# Beambreak_Array_L_-_Receiver.net
KiCad netlist of a schematic drawn in Altium Designer
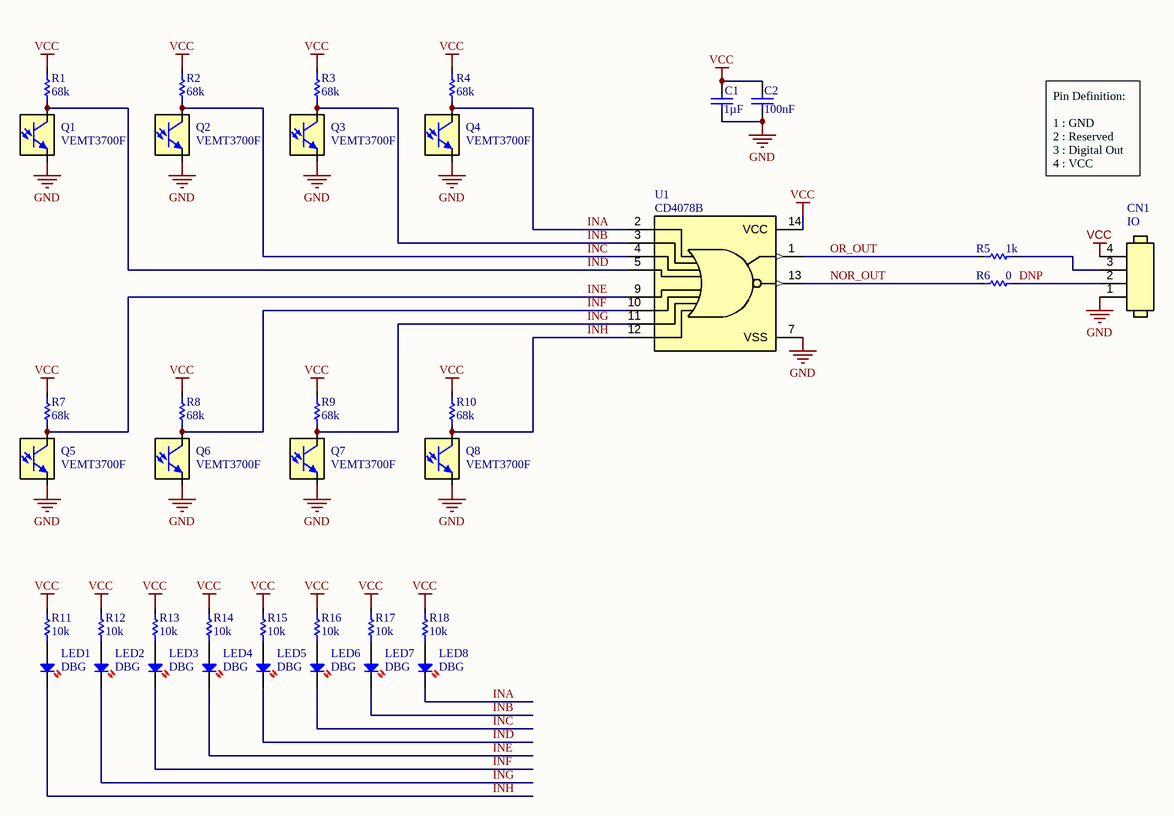
[diagram p0: Beambreak Array L - Receiver.SchDoc]

(export (version "E")
  (design (tool "Eeschema 10.0.6"))
  (components
    (comp (ref "C1")
      (value "1µF")
      (footprint "CAP_CHIP_0603")
      (description "0603 Multilayer Ceramic Capacitors MLCC")
      (fields (field (name "PARTNUMBER") "CL10A105KB8NNNC") (field (name "TOLERANCE") "10%"))
      (libsource (lib "Sainsbury Wellcome Centre") (part "Cap"))
    )
    (comp (ref "C2")
      (value "100nF")
      (footprint "CAP_CHIP_0603")
      (description "0603 Multilayer Ceramic Capacitors MLCC")
      (fields (field (name "TOLERANCE") "10%") (field (name "PARTNUMBER") "CC0603KRX7R9BB104"))
      (libsource (lib "Sainsbury Wellcome Centre") (part "Cap"))
    )
    (comp (ref "CN1")
      (value "IO")
      (footprint "MOLEX_1.25_4P")
      (description "Conn Shrouded Header (3 Sides) HDR 4 POS 1.25mm Solder ST Top Entry SMD PicoBlade™ T/R")
      (fields (field (name "PARTNUMBER") "53398-0471"))
      (libsource (lib "Sainsbury Wellcome Centre") (part "Wire to Board 1x4"))
    )
    (comp (ref "LED1")
      (value "DBG")
      (footprint "LED_CHIP_0805")
      (description "Red 0805 Light Emitting Diodes (LED) ROHS")
      (fields (field (name "PARTNUMBER") "NCD0805R1"))
      (libsource (lib "Sainsbury Wellcome Centre") (part "LED-RED"))
    )
    (comp (ref "LED2")
      (value "DBG")
      (footprint "LED_CHIP_0805")
      (description "Red 0805 Light Emitting Diodes (LED) ROHS")
      (fields (field (name "PARTNUMBER") "NCD0805R1"))
      (libsource (lib "Sainsbury Wellcome Centre") (part "LED-RED"))
    )
    (comp (ref "LED3")
      (value "DBG")
      (footprint "LED_CHIP_0805")
      (description "Red 0805 Light Emitting Diodes (LED) ROHS")
      (fields (field (name "PARTNUMBER") "NCD0805R1"))
      (libsource (lib "Sainsbury Wellcome Centre") (part "LED-RED"))
    )
    (comp (ref "LED4")
      (value "DBG")
      (footprint "LED_CHIP_0805")
      (description "Red 0805 Light Emitting Diodes (LED) ROHS")
      (fields (field (name "PARTNUMBER") "NCD0805R1"))
      (libsource (lib "Sainsbury Wellcome Centre") (part "LED-RED"))
    )
    (comp (ref "LED5")
      (value "DBG")
      (footprint "LED_CHIP_0805")
      (description "Red 0805 Light Emitting Diodes (LED) ROHS")
      (fields (field (name "PARTNUMBER") "NCD0805R1"))
      (libsource (lib "Sainsbury Wellcome Centre") (part "LED-RED"))
    )
    (comp (ref "LED6")
      (value "DBG")
      (footprint "LED_CHIP_0805")
      (description "Red 0805 Light Emitting Diodes (LED) ROHS")
      (fields (field (name "PARTNUMBER") "NCD0805R1"))
      (libsource (lib "Sainsbury Wellcome Centre") (part "LED-RED"))
    )
    (comp (ref "LED7")
      (value "DBG")
      (footprint "LED_CHIP_0805")
      (description "Red 0805 Light Emitting Diodes (LED) ROHS")
      (fields (field (name "PARTNUMBER") "NCD0805R1"))
      (libsource (lib "Sainsbury Wellcome Centre") (part "LED-RED"))
    )
    (comp (ref "LED8")
      (value "DBG")
      (footprint "LED_CHIP_0805")
      (description "Red 0805 Light Emitting Diodes (LED) ROHS")
      (fields (field (name "PARTNUMBER") "NCD0805R1"))
      (libsource (lib "Sainsbury Wellcome Centre") (part "LED-RED"))
    )
    (comp (ref "Q1")
      (value "VEMT3700F")
      (footprint "PT_3528_NPN")
      (description "No Phototransistor IR Chip Silicon 940nm 2-Pin PLCC T/R")
      (fields (field (name "PARTNUMBER") "VEMT3700F-GS08"))
      (libsource (lib "Sainsbury Wellcome Centre") (part "Phototransistors_1C2E"))
    )
    (comp (ref "Q2")
      (value "VEMT3700F")
      (footprint "PT_3528_NPN")
      (description "No Phototransistor IR Chip Silicon 940nm 2-Pin PLCC T/R")
      (fields (field (name "PARTNUMBER") "VEMT3700F-GS08"))
      (libsource (lib "Sainsbury Wellcome Centre") (part "Phototransistors_1C2E"))
    )
    (comp (ref "Q3")
      (value "VEMT3700F")
      (footprint "PT_3528_NPN")
      (description "No Phototransistor IR Chip Silicon 940nm 2-Pin PLCC T/R")
      (fields (field (name "PARTNUMBER") "VEMT3700F-GS08"))
      (libsource (lib "Sainsbury Wellcome Centre") (part "Phototransistors_1C2E"))
    )
    (comp (ref "Q4")
      (value "VEMT3700F")
      (footprint "PT_3528_NPN")
      (description "No Phototransistor IR Chip Silicon 940nm 2-Pin PLCC T/R")
      (fields (field (name "PARTNUMBER") "VEMT3700F-GS08"))
      (libsource (lib "Sainsbury Wellcome Centre") (part "Phototransistors_1C2E"))
    )
    (comp (ref "Q5")
      (value "VEMT3700F")
      (footprint "PT_3528_NPN")
      (description "No Phototransistor IR Chip Silicon 940nm 2-Pin PLCC T/R")
      (fields (field (name "PARTNUMBER") "VEMT3700F-GS08"))
      (libsource (lib "Sainsbury Wellcome Centre") (part "Phototransistors_1C2E"))
    )
    (comp (ref "Q6")
      (value "VEMT3700F")
      (footprint "PT_3528_NPN")
      (description "No Phototransistor IR Chip Silicon 940nm 2-Pin PLCC T/R")
      (fields (field (name "PARTNUMBER") "VEMT3700F-GS08"))
      (libsource (lib "Sainsbury Wellcome Centre") (part "Phototransistors_1C2E"))
    )
    (comp (ref "Q7")
      (value "VEMT3700F")
      (footprint "PT_3528_NPN")
      (description "No Phototransistor IR Chip Silicon 940nm 2-Pin PLCC T/R")
      (fields (field (name "PARTNUMBER") "VEMT3700F-GS08"))
      (libsource (lib "Sainsbury Wellcome Centre") (part "Phototransistors_1C2E"))
    )
    (comp (ref "Q8")
      (value "VEMT3700F")
      (footprint "PT_3528_NPN")
      (description "No Phototransistor IR Chip Silicon 940nm 2-Pin PLCC T/R")
      (fields (field (name "PARTNUMBER") "VEMT3700F-GS08"))
      (libsource (lib "Sainsbury Wellcome Centre") (part "Phototransistors_1C2E"))
    )
    (comp (ref "R1")
      (value "68k")
      (footprint "RES_CHIP_0603")
      (description "100mW Thick Film Resistors 75V ±100ppm/℃ ±1% 0603 Chip Resistor")
      (fields (field (name "TOLERANCE") "1%") (field (name "PARTNUMBER") "0603WAF6802T5E"))
      (libsource (lib "Sainsbury Wellcome Centre") (part "Res"))
    )
    (comp (ref "R2")
      (value "68k")
      (footprint "RES_CHIP_0603")
      (description "100mW Thick Film Resistors 75V ±100ppm/℃ ±1% 0603 Chip Resistor")
      (fields (field (name "TOLERANCE") "1%") (field (name "PARTNUMBER") "0603WAF6802T5E"))
      (libsource (lib "Sainsbury Wellcome Centre") (part "Res"))
    )
    (comp (ref "R3")
      (value "68k")
      (footprint "RES_CHIP_0603")
      (description "100mW Thick Film Resistors 75V ±100ppm/℃ ±1% 0603 Chip Resistor")
      (fields (field (name "TOLERANCE") "1%") (field (name "PARTNUMBER") "0603WAF6802T5E"))
      (libsource (lib "Sainsbury Wellcome Centre") (part "Res"))
    )
    (comp (ref "R4")
      (value "68k")
      (footprint "RES_CHIP_0603")
      (description "100mW Thick Film Resistors 75V ±100ppm/℃ ±1% 0603 Chip Resistor")
      (fields (field (name "TOLERANCE") "1%") (field (name "PARTNUMBER") "0603WAF6802T5E"))
      (libsource (lib "Sainsbury Wellcome Centre") (part "Res"))
    )
    (comp (ref "R5")
      (value "1k")
      (footprint "RES_CHIP_0603")
      (description "100mW Thick Film Resistors 75V ±100ppm/℃ ±1% 0603 Chip Resistor")
      (fields (field (name "PARTNUMBER") "0603WAF1001T5E") (field (name "TOLERANCE") "1%"))
      (libsource (lib "Sainsbury Wellcome Centre") (part "Res"))
    )
    (comp (ref "R6")
      (value "0")
      (footprint "RES_CHIP_0603")
      (description "100mW Thick Film Resistors 75V ±100ppm/℃ ±1% 0603 Chip Resistor")
      (fields
        (field (name "TOLERANCE") "1%")
        (field (name "PARTNUMBER") "0603WAF0000T5E")
        (field (name "LCSC PART N.") "DNP")
      )
      (libsource (lib "Sainsbury Wellcome Centre") (part "Res"))
    )
    (comp (ref "R7")
      (value "68k")
      (footprint "RES_CHIP_0603")
      (description "100mW Thick Film Resistors 75V ±100ppm/℃ ±1% 0603 Chip Resistor")
      (fields (field (name "TOLERANCE") "1%") (field (name "PARTNUMBER") "0603WAF6802T5E"))
      (libsource (lib "Sainsbury Wellcome Centre") (part "Res"))
    )
    (comp (ref "R8")
      (value "68k")
      (footprint "RES_CHIP_0603")
      (description "100mW Thick Film Resistors 75V ±100ppm/℃ ±1% 0603 Chip Resistor")
      (fields (field (name "TOLERANCE") "1%") (field (name "PARTNUMBER") "0603WAF6802T5E"))
      (libsource (lib "Sainsbury Wellcome Centre") (part "Res"))
    )
    (comp (ref "R9")
      (value "68k")
      (footprint "RES_CHIP_0603")
      (description "100mW Thick Film Resistors 75V ±100ppm/℃ ±1% 0603 Chip Resistor")
      (fields (field (name "TOLERANCE") "1%") (field (name "PARTNUMBER") "0603WAF6802T5E"))
      (libsource (lib "Sainsbury Wellcome Centre") (part "Res"))
    )
    (comp (ref "R10")
      (value "68k")
      (footprint "RES_CHIP_0603")
      (description "100mW Thick Film Resistors 75V ±100ppm/℃ ±1% 0603 Chip Resistor")
      (fields (field (name "TOLERANCE") "1%") (field (name "PARTNUMBER") "0603WAF6802T5E"))
      (libsource (lib "Sainsbury Wellcome Centre") (part "Res"))
    )
    (comp (ref "R11")
      (value "10k")
      (footprint "RES_CHIP_0603")
      (description "100mW Thick Film Resistors 75V ±100ppm/℃ ±1% 0603 Chip Resistor")
      (fields (field (name "PARTNUMBER") "0603WAF1002T5E") (field (name "TOLERANCE") "1%"))
      (libsource (lib "Sainsbury Wellcome Centre") (part "Res"))
    )
    (comp (ref "R12")
      (value "10k")
      (footprint "RES_CHIP_0603")
      (description "100mW Thick Film Resistors 75V ±100ppm/℃ ±1% 0603 Chip Resistor")
      (fields (field (name "PARTNUMBER") "0603WAF1002T5E") (field (name "TOLERANCE") "1%"))
      (libsource (lib "Sainsbury Wellcome Centre") (part "Res"))
    )
    (comp (ref "R13")
      (value "10k")
      (footprint "RES_CHIP_0603")
      (description "100mW Thick Film Resistors 75V ±100ppm/℃ ±1% 0603 Chip Resistor")
      (fields (field (name "PARTNUMBER") "0603WAF1002T5E") (field (name "TOLERANCE") "1%"))
      (libsource (lib "Sainsbury Wellcome Centre") (part "Res"))
    )
    (comp (ref "R14")
      (value "10k")
      (footprint "RES_CHIP_0603")
      (description "100mW Thick Film Resistors 75V ±100ppm/℃ ±1% 0603 Chip Resistor")
      (fields (field (name "PARTNUMBER") "0603WAF1002T5E") (field (name "TOLERANCE") "1%"))
      (libsource (lib "Sainsbury Wellcome Centre") (part "Res"))
    )
    (comp (ref "R15")
      (value "10k")
      (footprint "RES_CHIP_0603")
      (description "100mW Thick Film Resistors 75V ±100ppm/℃ ±1% 0603 Chip Resistor")
      (fields (field (name "PARTNUMBER") "0603WAF1002T5E") (field (name "TOLERANCE") "1%"))
      (libsource (lib "Sainsbury Wellcome Centre") (part "Res"))
    )
    (comp (ref "R16")
      (value "10k")
      (footprint "RES_CHIP_0603")
      (description "100mW Thick Film Resistors 75V ±100ppm/℃ ±1% 0603 Chip Resistor")
      (fields (field (name "PARTNUMBER") "0603WAF1002T5E") (field (name "TOLERANCE") "1%"))
      (libsource (lib "Sainsbury Wellcome Centre") (part "Res"))
    )
    (comp (ref "R17")
      (value "10k")
      (footprint "RES_CHIP_0603")
      (description "100mW Thick Film Resistors 75V ±100ppm/℃ ±1% 0603 Chip Resistor")
      (fields (field (name "PARTNUMBER") "0603WAF1002T5E") (field (name "TOLERANCE") "1%"))
      (libsource (lib "Sainsbury Wellcome Centre") (part "Res"))
    )
    (comp (ref "R18")
      (value "10k")
      (footprint "RES_CHIP_0603")
      (description "100mW Thick Film Resistors 75V ±100ppm/℃ ±1% 0603 Chip Resistor")
      (fields (field (name "PARTNUMBER") "0603WAF1002T5E") (field (name "TOLERANCE") "1%"))
      (libsource (lib "Sainsbury Wellcome Centre") (part "Res"))
    )
    (comp (ref "U1")
      (value "CD4078B")
      (footprint "SOIC14")
      (description "IC GATE NOR/OR 8INPUT 14SOIC NOR/OR Gate Configurable 1 Circuit 8 Input 14-SOIC")
      (fields (field (name "PARTNUMBER") "CD4078BM96"))
      (libsource (lib "Sainsbury Wellcome Centre") (part "CD4078B"))
    )
  )
  (nets
    (net (code "1") (name "/INA") (class "Default")
      (node (ref "LED8") (pin "1") (pinfunction "K_1") (pintype "passive"))
      (node (ref "Q4") (pin "1") (pinfunction "C_1") (pintype "passive"))
      (node (ref "R4") (pin "1") (pinfunction "1_1") (pintype "passive"))
      (node (ref "U1") (pin "2") (pinfunction "1A_2") (pintype "passive"))
    )
    (net (code "2") (name "/INB") (class "Default")
      (node (ref "LED7") (pin "1") (pinfunction "K_1") (pintype "passive"))
      (node (ref "Q3") (pin "1") (pinfunction "C_1") (pintype "passive"))
      (node (ref "R3") (pin "1") (pinfunction "1_1") (pintype "passive"))
      (node (ref "U1") (pin "3") (pinfunction "1A_3") (pintype "passive"))
    )
    (net (code "3") (name "/INC") (class "Default")
      (node (ref "LED6") (pin "1") (pinfunction "K_1") (pintype "passive"))
      (node (ref "Q2") (pin "1") (pinfunction "C_1") (pintype "passive"))
      (node (ref "R2") (pin "1") (pinfunction "1_1") (pintype "passive"))
      (node (ref "U1") (pin "4") (pinfunction "1A_4") (pintype "passive"))
    )
    (net (code "4") (name "/IND") (class "Default")
      (node (ref "LED5") (pin "1") (pinfunction "K_1") (pintype "passive"))
      (node (ref "Q1") (pin "1") (pinfunction "C_1") (pintype "passive"))
      (node (ref "R1") (pin "1") (pinfunction "1_1") (pintype "passive"))
      (node (ref "U1") (pin "5") (pinfunction "1A_5") (pintype "passive"))
    )
    (net (code "5") (name "/INE") (class "Default")
      (node (ref "LED4") (pin "1") (pinfunction "K_1") (pintype "passive"))
      (node (ref "Q5") (pin "1") (pinfunction "C_1") (pintype "passive"))
      (node (ref "R7") (pin "1") (pinfunction "1_1") (pintype "passive"))
      (node (ref "U1") (pin "9") (pinfunction "1B_9") (pintype "passive"))
    )
    (net (code "6") (name "/INF") (class "Default")
      (node (ref "LED3") (pin "1") (pinfunction "K_1") (pintype "passive"))
      (node (ref "Q6") (pin "1") (pinfunction "C_1") (pintype "passive"))
      (node (ref "R8") (pin "1") (pinfunction "1_1") (pintype "passive"))
      (node (ref "U1") (pin "10") (pinfunction "2A_10") (pintype "passive"))
    )
    (net (code "7") (name "/ING") (class "Default")
      (node (ref "LED2") (pin "1") (pinfunction "K_1") (pintype "passive"))
      (node (ref "Q7") (pin "1") (pinfunction "C_1") (pintype "passive"))
      (node (ref "R9") (pin "1") (pinfunction "1_1") (pintype "passive"))
      (node (ref "U1") (pin "11") (pinfunction "2B_11") (pintype "passive"))
    )
    (net (code "8") (name "/INH") (class "Default")
      (node (ref "LED1") (pin "1") (pinfunction "K_1") (pintype "passive"))
      (node (ref "Q8") (pin "1") (pinfunction "C_1") (pintype "passive"))
      (node (ref "R10") (pin "1") (pinfunction "1_1") (pintype "passive"))
      (node (ref "U1") (pin "12") (pinfunction "1A_12") (pintype "passive"))
    )
    (net (code "9") (name "/NOR_OUT") (class "Default")
      (node (ref "R6") (pin "1") (pinfunction "1_1") (pintype "passive"))
      (node (ref "U1") (pin "13") (pinfunction "OUT_13") (pintype "output"))
    )
    (net (code "10") (name "/OR_OUT") (class "Default")
      (node (ref "R5") (pin "2") (pinfunction "2_2") (pintype "passive"))
      (node (ref "U1") (pin "1") (pinfunction "~{OUT}_1") (pintype "output"))
    )
    (net (code "11") (name "GND") (class "Default")
      (node (ref "C1") (pin "2") (pinfunction "2_2") (pintype "passive"))
      (node (ref "C2") (pin "1") (pinfunction "1_1") (pintype "passive"))
      (node (ref "CN1") (pin "1") (pinfunction "1_1") (pintype "passive"))
      (node (ref "Q1") (pin "2") (pinfunction "E_2") (pintype "passive"))
      (node (ref "Q2") (pin "2") (pinfunction "E_2") (pintype "passive"))
      (node (ref "Q3") (pin "2") (pinfunction "E_2") (pintype "passive"))
      (node (ref "Q4") (pin "2") (pinfunction "E_2") (pintype "passive"))
      (node (ref "Q5") (pin "2") (pinfunction "E_2") (pintype "passive"))
      (node (ref "Q6") (pin "2") (pinfunction "E_2") (pintype "passive"))
      (node (ref "Q7") (pin "2") (pinfunction "E_2") (pintype "passive"))
      (node (ref "Q8") (pin "2") (pinfunction "E_2") (pintype "passive"))
      (node (ref "U1") (pin "7") (pinfunction "VSS_7") (pintype "power_in"))
    )
    (net (code "12") (name "Net-(CN1-Pad2)") (class "Default")
      (node (ref "CN1") (pin "2") (pinfunction "2_2") (pintype "passive"))
      (node (ref "R6") (pin "2") (pinfunction "2_2") (pintype "passive"))
    )
    (net (code "13") (name "Net-(CN1-Pad3)") (class "Default")
      (node (ref "CN1") (pin "3") (pinfunction "3_3") (pintype "passive"))
      (node (ref "R5") (pin "1") (pinfunction "1_1") (pintype "passive"))
    )
    (net (code "14") (name "Net-(LED1-A)") (class "Default")
      (node (ref "LED1") (pin "2") (pinfunction "A_2") (pintype "passive"))
      (node (ref "R11") (pin "1") (pinfunction "1_1") (pintype "passive"))
    )
    (net (code "15") (name "Net-(LED2-A)") (class "Default")
      (node (ref "LED2") (pin "2") (pinfunction "A_2") (pintype "passive"))
      (node (ref "R12") (pin "1") (pinfunction "1_1") (pintype "passive"))
    )
    (net (code "16") (name "Net-(LED3-A)") (class "Default")
      (node (ref "LED3") (pin "2") (pinfunction "A_2") (pintype "passive"))
      (node (ref "R13") (pin "1") (pinfunction "1_1") (pintype "passive"))
    )
    (net (code "17") (name "Net-(LED4-A)") (class "Default")
      (node (ref "LED4") (pin "2") (pinfunction "A_2") (pintype "passive"))
      (node (ref "R14") (pin "1") (pinfunction "1_1") (pintype "passive"))
    )
    (net (code "18") (name "Net-(LED5-A)") (class "Default")
      (node (ref "LED5") (pin "2") (pinfunction "A_2") (pintype "passive"))
      (node (ref "R15") (pin "1") (pinfunction "1_1") (pintype "passive"))
    )
    (net (code "19") (name "Net-(LED6-A)") (class "Default")
      (node (ref "LED6") (pin "2") (pinfunction "A_2") (pintype "passive"))
      (node (ref "R16") (pin "1") (pinfunction "1_1") (pintype "passive"))
    )
    (net (code "20") (name "Net-(LED7-A)") (class "Default")
      (node (ref "LED7") (pin "2") (pinfunction "A_2") (pintype "passive"))
      (node (ref "R17") (pin "1") (pinfunction "1_1") (pintype "passive"))
    )
    (net (code "21") (name "Net-(LED8-A)") (class "Default")
      (node (ref "LED8") (pin "2") (pinfunction "A_2") (pintype "passive"))
      (node (ref "R18") (pin "1") (pinfunction "1_1") (pintype "passive"))
    )
    (net (code "22") (name "VCC") (class "Default")
      (node (ref "C1") (pin "1") (pinfunction "1_1") (pintype "passive"))
      (node (ref "C2") (pin "2") (pinfunction "2_2") (pintype "passive"))
      (node (ref "CN1") (pin "4") (pinfunction "4_4") (pintype "passive"))
      (node (ref "R1") (pin "2") (pinfunction "2_2") (pintype "passive"))
      (node (ref "R10") (pin "2") (pinfunction "2_2") (pintype "passive"))
      (node (ref "R11") (pin "2") (pinfunction "2_2") (pintype "passive"))
      (node (ref "R12") (pin "2") (pinfunction "2_2") (pintype "passive"))
      (node (ref "R13") (pin "2") (pinfunction "2_2") (pintype "passive"))
      (node (ref "R14") (pin "2") (pinfunction "2_2") (pintype "passive"))
      (node (ref "R15") (pin "2") (pinfunction "2_2") (pintype "passive"))
      (node (ref "R16") (pin "2") (pinfunction "2_2") (pintype "passive"))
      (node (ref "R17") (pin "2") (pinfunction "2_2") (pintype "passive"))
      (node (ref "R18") (pin "2") (pinfunction "2_2") (pintype "passive"))
      (node (ref "R2") (pin "2") (pinfunction "2_2") (pintype "passive"))
      (node (ref "R3") (pin "2") (pinfunction "2_2") (pintype "passive"))
      (node (ref "R4") (pin "2") (pinfunction "2_2") (pintype "passive"))
      (node (ref "R7") (pin "2") (pinfunction "2_2") (pintype "passive"))
      (node (ref "R8") (pin "2") (pinfunction "2_2") (pintype "passive"))
      (node (ref "R9") (pin "2") (pinfunction "2_2") (pintype "passive"))
      (node (ref "U1") (pin "14") (pinfunction "VCC_14") (pintype "power_in"))
    )
  )
)
